# PIC_Schematic.net
KiCad netlist of a schematic drawn in EAGLE
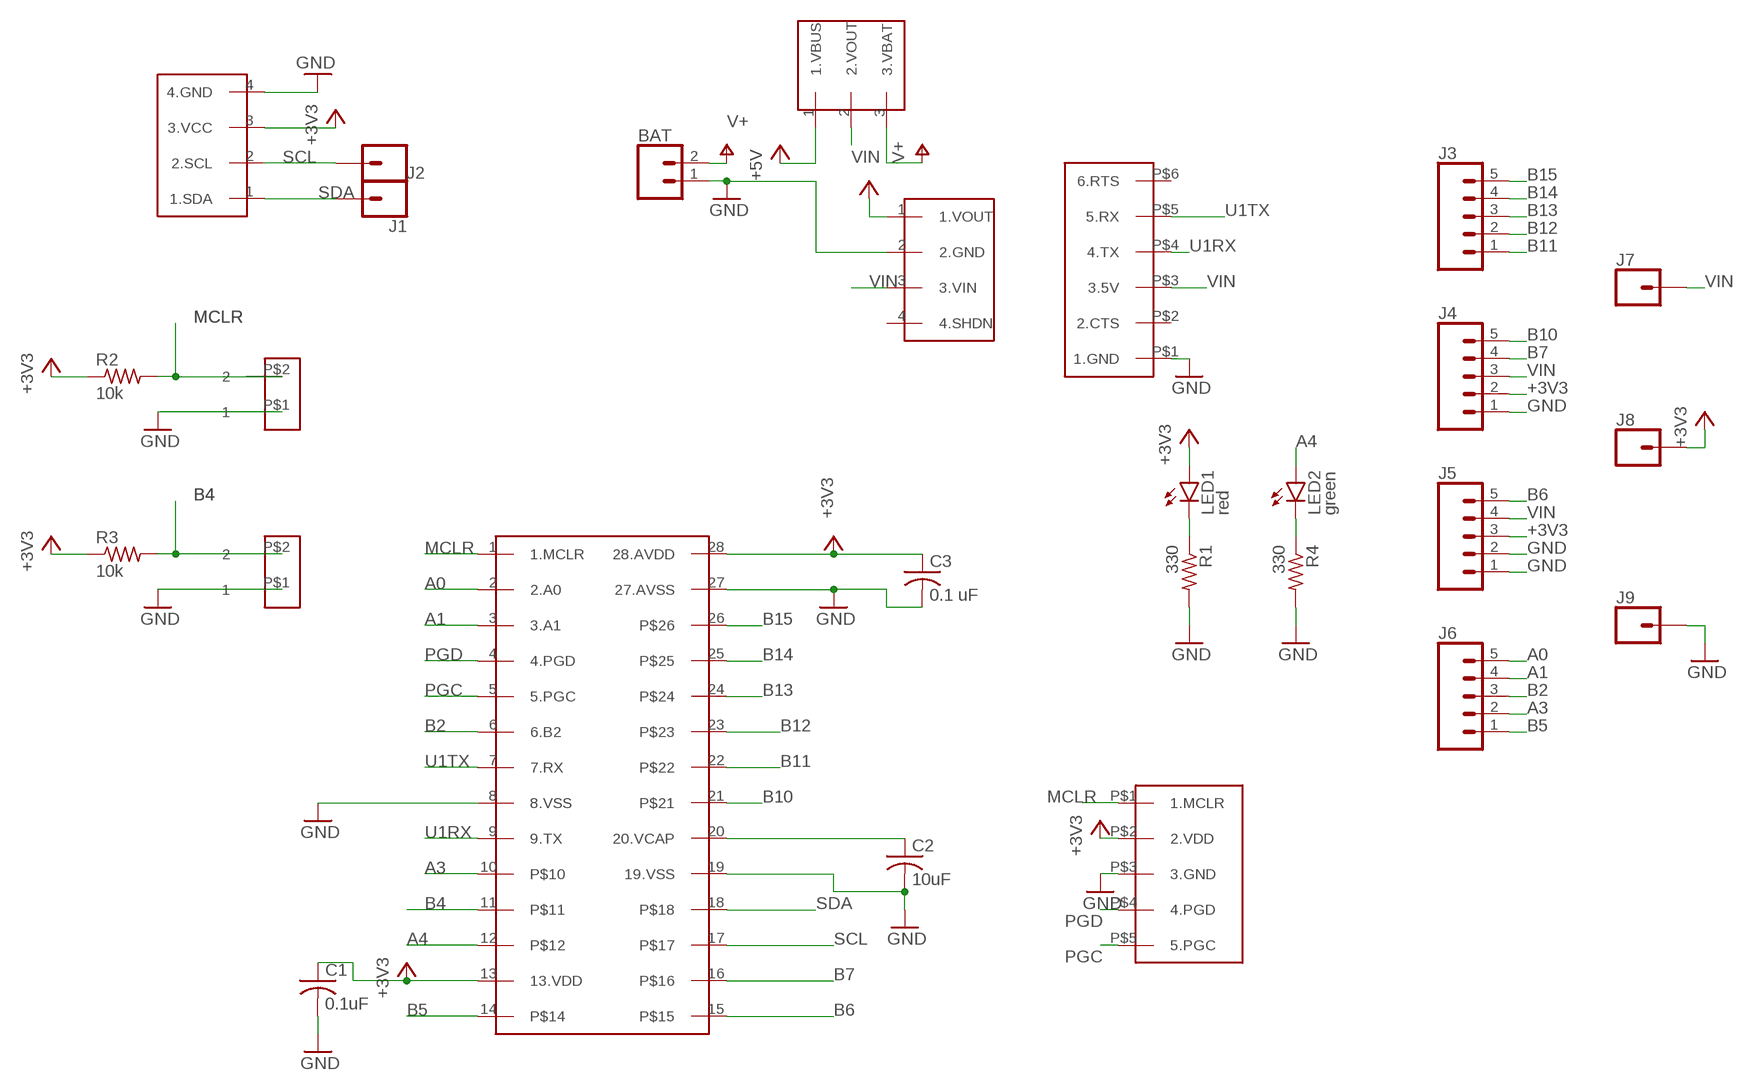
[diagram p0: schematic, sheet 1]

(export (version "E")
  (design (tool "Eeschema 10.0.6"))
  (components
    (comp (ref "BAT")
      (value "CONN_02")
      (footprint "eagle-import:1X02")
      (libsource (lib "eagle-import") (part "CONN_02"))
    )
    (comp (ref "C1")
      (value "0.1uF")
      (footprint "eagle-import:C025-024X044")
      (libsource (lib "eagle-import") (part "C-US025-024X044"))
    )
    (comp (ref "C2")
      (value "10uF")
      (footprint "eagle-import:C025-024X044")
      (libsource (lib "eagle-import") (part "C-US025-024X044"))
    )
    (comp (ref "C3")
      (value "0.1 uF")
      (footprint "eagle-import:C025-024X044")
      (libsource (lib "eagle-import") (part "C-US025-024X044"))
    )
    (comp (ref "J1")
      (value "CONN_01")
      (footprint "eagle-import:1X01")
      (libsource (lib "eagle-import") (part "CONN_01"))
    )
    (comp (ref "J2")
      (value "CONN_01")
      (footprint "eagle-import:1X01")
      (libsource (lib "eagle-import") (part "CONN_01"))
    )
    (comp (ref "J3")
      (value "CONN_05")
      (footprint "eagle-import:1X05")
      (libsource (lib "eagle-import") (part "CONN_05"))
    )
    (comp (ref "J4")
      (value "CONN_05")
      (footprint "eagle-import:1X05")
      (libsource (lib "eagle-import") (part "CONN_05"))
    )
    (comp (ref "J5")
      (value "CONN_05")
      (footprint "eagle-import:1X05")
      (libsource (lib "eagle-import") (part "CONN_05"))
    )
    (comp (ref "J6")
      (value "CONN_05")
      (footprint "eagle-import:1X05")
      (libsource (lib "eagle-import") (part "CONN_05"))
    )
    (comp (ref "J7")
      (value "CONN_01")
      (footprint "eagle-import:1X01")
      (libsource (lib "eagle-import") (part "CONN_01"))
    )
    (comp (ref "J8")
      (value "CONN_01")
      (footprint "eagle-import:1X01")
      (libsource (lib "eagle-import") (part "CONN_01"))
    )
    (comp (ref "J9")
      (value "CONN_01")
      (footprint "eagle-import:1X01")
      (libsource (lib "eagle-import") (part "CONN_01"))
    )
    (comp (ref "LED1")
      (value "red")
      (footprint "eagle-import:LED3MM")
      (libsource (lib "eagle-import") (part "LED3MM"))
    )
    (comp (ref "LED2")
      (value "green")
      (footprint "eagle-import:LED3MM")
      (libsource (lib "eagle-import") (part "LED3MM"))
    )
    (comp (ref "R1")
      (value "330")
      (footprint "eagle-import:0207_10")
      (libsource (lib "eagle-import") (part "R-US_0207/10"))
    )
    (comp (ref "R2")
      (value "10k")
      (footprint "eagle-import:0207_10")
      (libsource (lib "eagle-import") (part "R-US_0207/10"))
    )
    (comp (ref "R3")
      (value "10k")
      (footprint "eagle-import:0207_10")
      (libsource (lib "eagle-import") (part "R-US_0207/10"))
    )
    (comp (ref "R4")
      (value "330")
      (footprint "eagle-import:0207_10")
      (libsource (lib "eagle-import") (part "R-US_0207/10"))
    )
    (comp (ref "U$1")
      (value "PIC32")
      (footprint "eagle-import:DIL28-3")
      (libsource (lib "eagle-import") (part "PIC32"))
    )
    (comp (ref "U$2")
      (value "CP2104")
      (footprint "eagle-import:CP2104")
      (libsource (lib "eagle-import") (part "CP2104"))
    )
    (comp (ref "U$3")
      (value "SLIDE")
      (footprint "eagle-import:SLIDE")
      (libsource (lib "eagle-import") (part "SLIDE"))
    )
    (comp (ref "U$4")
      (value "VOLTREG")
      (footprint "eagle-import:VOLTREG")
      (libsource (lib "eagle-import") (part "VOLTREG"))
    )
    (comp (ref "U$5")
      (value "SNAP")
      (footprint "eagle-import:SNAP")
      (libsource (lib "eagle-import") (part "SNAP"))
    )
    (comp (ref "U$6")
      (value "PUSH")
      (footprint "eagle-import:PUSH")
      (libsource (lib "eagle-import") (part "PUSH"))
    )
    (comp (ref "U$7")
      (value "PUSH")
      (footprint "eagle-import:PUSH")
      (libsource (lib "eagle-import") (part "PUSH"))
    )
    (comp (ref "U$8")
      (value "OLED")
      (footprint "eagle-import:OLED")
      (libsource (lib "eagle-import") (part "OLED"))
    )
  )
  (nets
    (net (code "1") (name "+3V3") (class "Default")
      (node (ref "C1") (pin "1") (pinfunction "1_1") (pintype "passive"))
      (node (ref "C3") (pin "1") (pinfunction "1_1") (pintype "passive"))
      (node (ref "J4") (pin "2") (pinfunction "2_2") (pintype "passive"))
      (node (ref "J5") (pin "3") (pinfunction "3_3") (pintype "passive"))
      (node (ref "J8") (pin "1") (pinfunction "1_1") (pintype "passive"))
      (node (ref "LED1") (pin "A") (pinfunction "A_A") (pintype "passive"))
      (node (ref "R2") (pin "1") (pinfunction "1_1") (pintype "passive"))
      (node (ref "R3") (pin "1") (pinfunction "1_1") (pintype "passive"))
      (node (ref "U$1") (pin "13") (pinfunction "13.VDD_13") (pintype "bidirectional"))
      (node (ref "U$1") (pin "28") (pinfunction "28.AVDD_28") (pintype "bidirectional"))
      (node (ref "U$4") (pin "1") (pinfunction "1.VOUT_1") (pintype "bidirectional"))
      (node (ref "U$5") (pin "P$2") (pinfunction "2.VDD_P$2") (pintype "bidirectional"))
      (node (ref "U$8") (pin "3") (pinfunction "3.VCC_3") (pintype "bidirectional"))
    )
    (net (code "2") (name "+5V") (class "Default")
      (node (ref "U$3") (pin "1") (pinfunction "1.VBUS_1") (pintype "bidirectional"))
    )
    (net (code "3") (name "/A0") (class "Default")
      (node (ref "J6") (pin "5") (pinfunction "5_5") (pintype "passive"))
      (node (ref "U$1") (pin "2") (pinfunction "2.A0_2") (pintype "bidirectional"))
    )
    (net (code "4") (name "/A1") (class "Default")
      (node (ref "J6") (pin "4") (pinfunction "4_4") (pintype "passive"))
      (node (ref "U$1") (pin "3") (pinfunction "3.A1_3") (pintype "bidirectional"))
    )
    (net (code "5") (name "/A3") (class "Default")
      (node (ref "J6") (pin "2") (pinfunction "2_2") (pintype "passive"))
      (node (ref "U$1") (pin "10") (pinfunction "P$10_10") (pintype "bidirectional"))
    )
    (net (code "6") (name "/A4") (class "Default")
      (node (ref "LED2") (pin "A") (pinfunction "A_A") (pintype "passive"))
      (node (ref "U$1") (pin "12") (pinfunction "P$12_12") (pintype "bidirectional"))
    )
    (net (code "7") (name "/B2") (class "Default")
      (node (ref "J6") (pin "3") (pinfunction "3_3") (pintype "passive"))
      (node (ref "U$1") (pin "6") (pinfunction "6.B2_6") (pintype "bidirectional"))
    )
    (net (code "8") (name "/B4") (class "Default")
      (node (ref "R3") (pin "2") (pinfunction "2_2") (pintype "passive"))
      (node (ref "U$1") (pin "11") (pinfunction "P$11_11") (pintype "bidirectional"))
      (node (ref "U$7") (pin "P$2") (pinfunction "2_P$2") (pintype "bidirectional"))
    )
    (net (code "9") (name "/B5") (class "Default")
      (node (ref "J6") (pin "1") (pinfunction "1_1") (pintype "passive"))
      (node (ref "U$1") (pin "14") (pinfunction "P$14_14") (pintype "bidirectional"))
    )
    (net (code "10") (name "/B6") (class "Default")
      (node (ref "J5") (pin "5") (pinfunction "5_5") (pintype "passive"))
      (node (ref "U$1") (pin "15") (pinfunction "P$15_15") (pintype "bidirectional"))
    )
    (net (code "11") (name "/B7") (class "Default")
      (node (ref "J4") (pin "4") (pinfunction "4_4") (pintype "passive"))
      (node (ref "U$1") (pin "16") (pinfunction "P$16_16") (pintype "bidirectional"))
    )
    (net (code "12") (name "/B10") (class "Default")
      (node (ref "J4") (pin "5") (pinfunction "5_5") (pintype "passive"))
      (node (ref "U$1") (pin "21") (pinfunction "P$21_21") (pintype "bidirectional"))
    )
    (net (code "13") (name "/B11") (class "Default")
      (node (ref "J3") (pin "1") (pinfunction "1_1") (pintype "passive"))
      (node (ref "U$1") (pin "22") (pinfunction "P$22_22") (pintype "bidirectional"))
    )
    (net (code "14") (name "/B12") (class "Default")
      (node (ref "J3") (pin "2") (pinfunction "2_2") (pintype "passive"))
      (node (ref "U$1") (pin "23") (pinfunction "P$23_23") (pintype "bidirectional"))
    )
    (net (code "15") (name "/B13") (class "Default")
      (node (ref "J3") (pin "3") (pinfunction "3_3") (pintype "passive"))
      (node (ref "U$1") (pin "24") (pinfunction "P$24_24") (pintype "bidirectional"))
    )
    (net (code "16") (name "/B14") (class "Default")
      (node (ref "J3") (pin "4") (pinfunction "4_4") (pintype "passive"))
      (node (ref "U$1") (pin "25") (pinfunction "P$25_25") (pintype "bidirectional"))
    )
    (net (code "17") (name "/B15") (class "Default")
      (node (ref "J3") (pin "5") (pinfunction "5_5") (pintype "passive"))
      (node (ref "U$1") (pin "26") (pinfunction "P$26_26") (pintype "bidirectional"))
    )
    (net (code "18") (name "/MCLR") (class "Default")
      (node (ref "R2") (pin "2") (pinfunction "2_2") (pintype "passive"))
      (node (ref "U$1") (pin "1") (pinfunction "1.MCLR_1") (pintype "bidirectional"))
      (node (ref "U$5") (pin "P$1") (pinfunction "1.MCLR_P$1") (pintype "bidirectional"))
      (node (ref "U$6") (pin "P$2") (pinfunction "2_P$2") (pintype "bidirectional"))
    )
    (net (code "19") (name "/PGC") (class "Default")
      (node (ref "U$1") (pin "5") (pinfunction "5.PGC_5") (pintype "bidirectional"))
      (node (ref "U$5") (pin "P$5") (pinfunction "5.PGC_P$5") (pintype "bidirectional"))
    )
    (net (code "20") (name "/PGD") (class "Default")
      (node (ref "U$1") (pin "4") (pinfunction "4.PGD_4") (pintype "bidirectional"))
      (node (ref "U$5") (pin "P$4") (pinfunction "4.PGD_P$4") (pintype "bidirectional"))
    )
    (net (code "21") (name "/SCL") (class "Default")
      (node (ref "J2") (pin "1") (pinfunction "1_1") (pintype "passive"))
      (node (ref "U$1") (pin "17") (pinfunction "P$17_17") (pintype "bidirectional"))
      (node (ref "U$8") (pin "2") (pinfunction "2.SCL_2") (pintype "bidirectional"))
    )
    (net (code "22") (name "/SDA") (class "Default")
      (node (ref "J1") (pin "1") (pinfunction "1_1") (pintype "passive"))
      (node (ref "U$1") (pin "18") (pinfunction "P$18_18") (pintype "bidirectional"))
      (node (ref "U$8") (pin "1") (pinfunction "1.SDA_1") (pintype "bidirectional"))
    )
    (net (code "23") (name "/U1RX") (class "Default")
      (node (ref "U$1") (pin "9") (pinfunction "9.TX_9") (pintype "bidirectional"))
      (node (ref "U$2") (pin "P$4") (pinfunction "4.TX_P$4") (pintype "bidirectional"))
    )
    (net (code "24") (name "/U1TX") (class "Default")
      (node (ref "U$1") (pin "7") (pinfunction "7.RX_7") (pintype "bidirectional"))
      (node (ref "U$2") (pin "P$5") (pinfunction "5.RX_P$5") (pintype "bidirectional"))
    )
    (net (code "25") (name "/VIN") (class "Default")
      (node (ref "J4") (pin "3") (pinfunction "3_3") (pintype "passive"))
      (node (ref "J5") (pin "4") (pinfunction "4_4") (pintype "passive"))
      (node (ref "J7") (pin "1") (pinfunction "1_1") (pintype "passive"))
      (node (ref "U$2") (pin "P$3") (pinfunction "3.5V_P$3") (pintype "bidirectional"))
      (node (ref "U$3") (pin "2") (pinfunction "2.VOUT_2") (pintype "bidirectional"))
      (node (ref "U$4") (pin "3") (pinfunction "3.VIN_3") (pintype "bidirectional"))
    )
    (net (code "26") (name "GND") (class "Default")
      (node (ref "BAT") (pin "1") (pinfunction "1_1") (pintype "passive"))
      (node (ref "C1") (pin "2") (pinfunction "2_2") (pintype "passive"))
      (node (ref "C2") (pin "2") (pinfunction "2_2") (pintype "passive"))
      (node (ref "C3") (pin "2") (pinfunction "2_2") (pintype "passive"))
      (node (ref "J4") (pin "1") (pinfunction "1_1") (pintype "passive"))
      (node (ref "J5") (pin "1") (pinfunction "1_1") (pintype "passive"))
      (node (ref "J5") (pin "2") (pinfunction "2_2") (pintype "passive"))
      (node (ref "J9") (pin "1") (pinfunction "1_1") (pintype "passive"))
      (node (ref "R1") (pin "2") (pinfunction "2_2") (pintype "passive"))
      (node (ref "R4") (pin "2") (pinfunction "2_2") (pintype "passive"))
      (node (ref "U$1") (pin "19") (pinfunction "19.VSS_19") (pintype "bidirectional"))
      (node (ref "U$1") (pin "27") (pinfunction "27.AVSS_27") (pintype "bidirectional"))
      (node (ref "U$1") (pin "8") (pinfunction "8.VSS_8") (pintype "bidirectional"))
      (node (ref "U$2") (pin "P$1") (pinfunction "1.GND_P$1") (pintype "bidirectional"))
      (node (ref "U$4") (pin "2") (pinfunction "2.GND_2") (pintype "bidirectional"))
      (node (ref "U$5") (pin "P$3") (pinfunction "3.GND_P$3") (pintype "bidirectional"))
      (node (ref "U$6") (pin "P$1") (pinfunction "1_P$1") (pintype "bidirectional"))
      (node (ref "U$7") (pin "P$1") (pinfunction "1_P$1") (pintype "bidirectional"))
      (node (ref "U$8") (pin "4") (pinfunction "4.GND_4") (pintype "bidirectional"))
    )
    (net (code "27") (name "Net-(LED1-C)") (class "Default")
      (node (ref "LED1") (pin "K") (pinfunction "C_K") (pintype "passive"))
      (node (ref "R1") (pin "1") (pinfunction "1_1") (pintype "passive"))
    )
    (net (code "28") (name "Net-(LED2-C)") (class "Default")
      (node (ref "LED2") (pin "K") (pinfunction "C_K") (pintype "passive"))
      (node (ref "R4") (pin "1") (pinfunction "1_1") (pintype "passive"))
    )
    (net (code "29") (name "Net-(U$1-20.VCAP)") (class "Default")
      (node (ref "C2") (pin "1") (pinfunction "1_1") (pintype "passive"))
      (node (ref "U$1") (pin "20") (pinfunction "20.VCAP_20") (pintype "bidirectional"))
    )
    (net (code "30") (name "V+") (class "Default")
      (node (ref "BAT") (pin "2") (pinfunction "2_2") (pintype "passive"))
      (node (ref "U$3") (pin "3") (pinfunction "3.VBAT_3") (pintype "bidirectional"))
    )
    (net (code "31") (name "unconnected-(U$2-2.CTS-PadP$2)") (class "Default")
      (node (ref "U$2") (pin "P$2") (pinfunction "2.CTS_P$2") (pintype "bidirectional"))
    )
    (net (code "32") (name "unconnected-(U$2-6.RTS-PadP$6)") (class "Default")
      (node (ref "U$2") (pin "P$6") (pinfunction "6.RTS_P$6") (pintype "bidirectional"))
    )
    (net (code "33") (name "unconnected-(U$4-4.SHDN-Pad4)") (class "Default")
      (node (ref "U$4") (pin "4") (pinfunction "4.SHDN_4") (pintype "bidirectional"))
    )
  )
)
